# zgrzewarka2.net
KiCad netlist of a schematic drawn in EAGLE
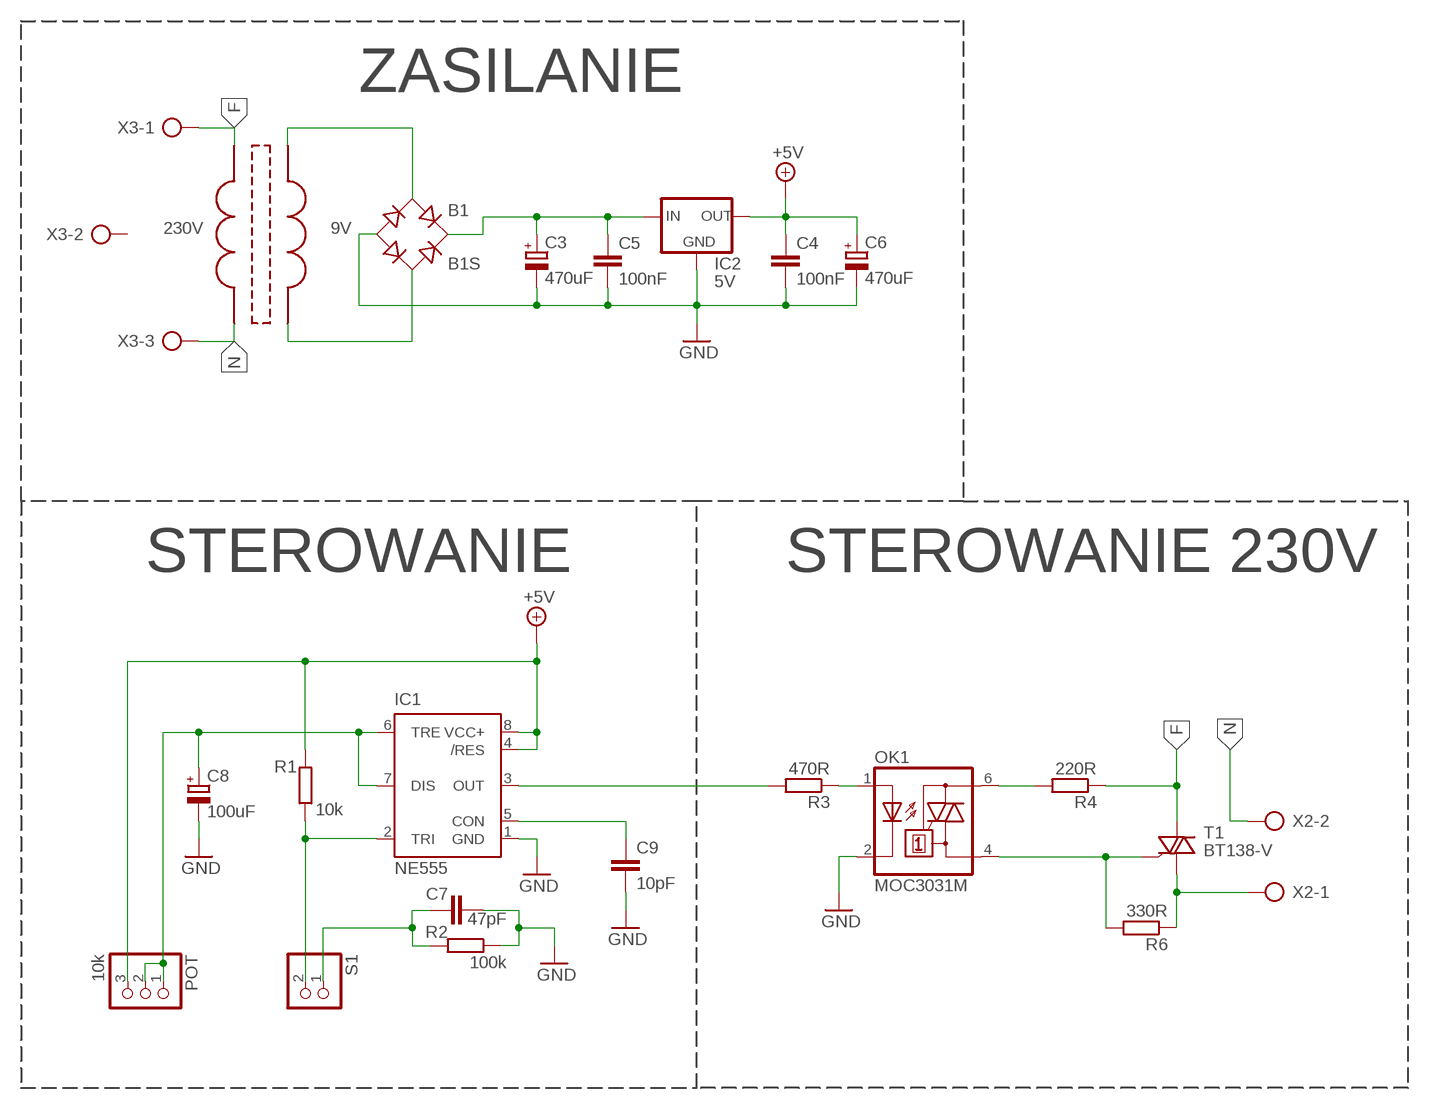
[diagram p0: schematic, sheet 1]

(export (version "E")
  (design (tool "Eeschema 10.0.6"))
  (components
    (comp (ref "B1")
      (value "B1S")
      (footprint "eagle-import:MBS")
      (libsource (lib "eagle-import") (part "BS1"))
    )
    (comp (ref "C3")
      (value "470uF")
      (footprint "eagle-import:C5-8,5")
      (libsource (lib "eagle-import") (part "C-EU-POL'''"))
    )
    (comp (ref "C4")
      (value "100nF")
      (footprint "eagle-import:C50-45-75")
      (libsource (lib "eagle-import") (part "C-EU050-045-075"))
    )
    (comp (ref "C5")
      (value "100nF")
      (footprint "eagle-import:C50-45-75")
      (libsource (lib "eagle-import") (part "C-EU050-045-075"))
    )
    (comp (ref "C6")
      (value "470uF")
      (footprint "eagle-import:C5-8,5")
      (libsource (lib "eagle-import") (part "C-EU-POL'''"))
    )
    (comp (ref "C7")
      (value "47pF")
      (footprint "eagle-import:C50-45-75")
      (libsource (lib "eagle-import") (part "C-EU050-045-075"))
    )
    (comp (ref "C8")
      (value "100uF")
      (footprint "eagle-import:C5-8,5")
      (libsource (lib "eagle-import") (part "C-EU-POL'''"))
    )
    (comp (ref "C9")
      (value "10pF")
      (footprint "eagle-import:C50-45-75")
      (libsource (lib "eagle-import") (part "C-EU050-045-075"))
    )
    (comp (ref "IC1")
      (value "NE555")
      (footprint "eagle-import:DIL-08")
      (fields (field (name "MF") "Arrow Electronics") (field (name "MPN") "NE555N"))
      (libsource (lib "eagle-import") (part "NE555"))
    )
    (comp (ref "IC2")
      (value "5V")
      (footprint "eagle-import:78LXX")
      (libsource (lib "eagle-import") (part "78LXX"))
    )
    (comp (ref "OK1")
      (value "MOC3031M")
      (footprint "eagle-import:DIL06")
      (fields (field (name "MF") "FAIRCHILD SEMICONDUCTOR"))
      (libsource (lib "eagle-import") (part "MOC3031M"))
    )
    (comp (ref "POT")
      (value "10k")
      (footprint "eagle-import:1X03")
      (libsource (lib "eagle-import") (part "PINHD-1X3"))
    )
    (comp (ref "R1")
      (value "10k")
      (footprint "eagle-import:204_7")
      (libsource (lib "eagle-import") (part "R-EU7"))
    )
    (comp (ref "R2")
      (value "100k")
      (footprint "eagle-import:204_7")
      (libsource (lib "eagle-import") (part "R-EU7"))
    )
    (comp (ref "R3")
      (value "470R")
      (footprint "eagle-import:204_7")
      (libsource (lib "eagle-import") (part "R-EU7"))
    )
    (comp (ref "R4")
      (value "220R")
      (footprint "eagle-import:204_7")
      (libsource (lib "eagle-import") (part "R-EU7"))
    )
    (comp (ref "R6")
      (value "330R")
      (footprint "eagle-import:204_7")
      (libsource (lib "eagle-import") (part "R-EU7"))
    )
    (comp (ref "S1")
      (value "PINHD-1X2")
      (footprint "eagle-import:1X02")
      (libsource (lib "eagle-import") (part "PINHD-1X2"))
    )
    (comp (ref "T1")
      (value "BT138-V")
      (footprint "eagle-import:TO220BV")
      (libsource (lib "eagle-import") (part "BT138-V"))
    )
    (comp (ref "U$1")
      (value "TRAFO-9V")
      (footprint "eagle-import:OBUDOWA1")
      (libsource (lib "eagle-import") (part "TRAFO-9V"))
    )
    (comp (ref "X2")
      (value "AK300/2")
      (footprint "eagle-import:AK300_2")
      (libsource (lib "eagle-import") (part "AK300/2"))
    )
    (comp (ref "X3")
      (value "AK300/3")
      (footprint "eagle-import:AK300_3")
      (libsource (lib "eagle-import") (part "AK300/3"))
    )
  )
  (nets
    (net (code "1") (name "+5V") (class "Default")
      (node (ref "C4") (pin "P$1") (pinfunction "1_P$1") (pintype "passive"))
      (node (ref "C6") (pin "+") (pinfunction "+_+") (pintype "passive"))
      (node (ref "IC1") (pin "4") (pinfunction "/RES_4") (pintype "input"))
      (node (ref "IC1") (pin "8") (pinfunction "VCC+_8") (pintype "power_in"))
      (node (ref "IC2") (pin "OUT") (pinfunction "OUT_OUT") (pintype "passive"))
      (node (ref "POT") (pin "3") (pinfunction "3_3") (pintype "passive"))
      (node (ref "R1") (pin "P$2") (pinfunction "2_P$2") (pintype "passive"))
    )
    (net (code "2") (name "F") (class "Default")
      (node (ref "R4") (pin "P$1") (pinfunction "1_P$1") (pintype "passive"))
      (node (ref "T1") (pin "T2") (pinfunction "A2_T2") (pintype "passive"))
      (node (ref "U$1") (pin "230V-1") (pinfunction "230V-1_230V-1") (pintype "bidirectional"))
      (node (ref "X3") (pin "1") (pinfunction "KL_1") (pintype "passive"))
    )
    (net (code "3") (name "GND") (class "Default")
      (node (ref "B1") (pin "-") (pinfunction "-_-") (pintype "passive"))
      (node (ref "C3") (pin "-") (pinfunction "-_-") (pintype "passive"))
      (node (ref "C4") (pin "P$2") (pinfunction "2_P$2") (pintype "passive"))
      (node (ref "C5") (pin "P$2") (pinfunction "2_P$2") (pintype "passive"))
      (node (ref "C6") (pin "-") (pinfunction "-_-") (pintype "passive"))
      (node (ref "C7") (pin "P$2") (pinfunction "2_P$2") (pintype "passive"))
      (node (ref "C8") (pin "-") (pinfunction "-_-") (pintype "passive"))
      (node (ref "C9") (pin "P$2") (pinfunction "2_P$2") (pintype "passive"))
      (node (ref "IC1") (pin "1") (pinfunction "GND_1") (pintype "power_in"))
      (node (ref "IC2") (pin "GND") (pinfunction "GND_GND") (pintype "input"))
      (node (ref "OK1") (pin "2") (pinfunction "C_2") (pintype "passive"))
      (node (ref "R2") (pin "P$1") (pinfunction "1_P$1") (pintype "passive"))
    )
    (net (code "4") (name "N") (class "Default")
      (node (ref "U$1") (pin "230V-2") (pinfunction "230V-2_230V-2") (pintype "bidirectional"))
      (node (ref "X2") (pin "2") (pinfunction "KL_2") (pintype "passive"))
      (node (ref "X3") (pin "3") (pinfunction "KL_3") (pintype "passive"))
    )
    (net (code "5") (name "Net-(B1-PadAC1)") (class "Default")
      (node (ref "B1") (pin "AC1") (pinfunction "AC1_AC1") (pintype "passive"))
      (node (ref "U$1") (pin "9V-1") (pinfunction "9V-1_9V-1") (pintype "bidirectional"))
    )
    (net (code "6") (name "Net-(B1-PadAC2)") (class "Default")
      (node (ref "B1") (pin "AC2") (pinfunction "AC2_AC2") (pintype "passive"))
      (node (ref "U$1") (pin "9V-2") (pinfunction "9V-2_9V-2") (pintype "bidirectional"))
    )
    (net (code "7") (name "Net-(C5-1)") (class "Default")
      (node (ref "B1") (pin "+") (pinfunction "+_+") (pintype "passive"))
      (node (ref "C3") (pin "+") (pinfunction "+_+") (pintype "passive"))
      (node (ref "C5") (pin "P$1") (pinfunction "1_P$1") (pintype "passive"))
      (node (ref "IC2") (pin "IN") (pinfunction "IN_IN") (pintype "input"))
    )
    (net (code "8") (name "Net-(C7-1)") (class "Default")
      (node (ref "C7") (pin "P$1") (pinfunction "1_P$1") (pintype "passive"))
      (node (ref "R2") (pin "P$2") (pinfunction "2_P$2") (pintype "passive"))
      (node (ref "S1") (pin "1") (pinfunction "1_1") (pintype "passive"))
    )
    (net (code "9") (name "Net-(C9-1)") (class "Default")
      (node (ref "C9") (pin "P$1") (pinfunction "1_P$1") (pintype "passive"))
      (node (ref "IC1") (pin "5") (pinfunction "CON_5") (pintype "input"))
    )
    (net (code "10") (name "Net-(IC1-DIS)") (class "Default")
      (node (ref "C8") (pin "+") (pinfunction "+_+") (pintype "passive"))
      (node (ref "IC1") (pin "6") (pinfunction "TRE_6") (pintype "input"))
      (node (ref "IC1") (pin "7") (pinfunction "DIS_7") (pintype "input"))
      (node (ref "POT") (pin "1") (pinfunction "1_1") (pintype "passive"))
      (node (ref "POT") (pin "2") (pinfunction "2_2") (pintype "passive"))
    )
    (net (code "11") (name "Net-(IC1-OUT)") (class "Default")
      (node (ref "IC1") (pin "3") (pinfunction "OUT_3") (pintype "output"))
      (node (ref "R3") (pin "P$2") (pinfunction "2_P$2") (pintype "passive"))
    )
    (net (code "12") (name "Net-(IC1-TRI)") (class "Default")
      (node (ref "IC1") (pin "2") (pinfunction "TRI_2") (pintype "input"))
      (node (ref "R1") (pin "P$1") (pinfunction "1_P$1") (pintype "passive"))
      (node (ref "S1") (pin "2") (pinfunction "2_2") (pintype "passive"))
    )
    (net (code "13") (name "Net-(OK1-A)") (class "Default")
      (node (ref "OK1") (pin "1") (pinfunction "A_1") (pintype "passive"))
      (node (ref "R3") (pin "P$1") (pinfunction "1_P$1") (pintype "passive"))
    )
    (net (code "14") (name "Net-(OK1-A1)") (class "Default")
      (node (ref "OK1") (pin "4") (pinfunction "A1_4") (pintype "passive"))
      (node (ref "R6") (pin "P$2") (pinfunction "2_P$2") (pintype "passive"))
      (node (ref "T1") (pin "G") (pinfunction "G_G") (pintype "passive"))
    )
    (net (code "15") (name "Net-(OK1-A2)") (class "Default")
      (node (ref "OK1") (pin "6") (pinfunction "A2_6") (pintype "passive"))
      (node (ref "R4") (pin "P$2") (pinfunction "2_P$2") (pintype "passive"))
    )
    (net (code "16") (name "Net-(R6-1)") (class "Default")
      (node (ref "R6") (pin "P$1") (pinfunction "1_P$1") (pintype "passive"))
      (node (ref "T1") (pin "T1") (pinfunction "A1_T1") (pintype "passive"))
      (node (ref "X2") (pin "1") (pinfunction "KL_1") (pintype "passive"))
    )
    (net (code "17") (name "unconnected-(X3B-KL-Pad2)") (class "Default")
      (node (ref "X3") (pin "2") (pinfunction "KL_2") (pintype "passive"))
    )
  )
)
